# main.net
KiCad netlist of a schematic drawn in Altium Designer
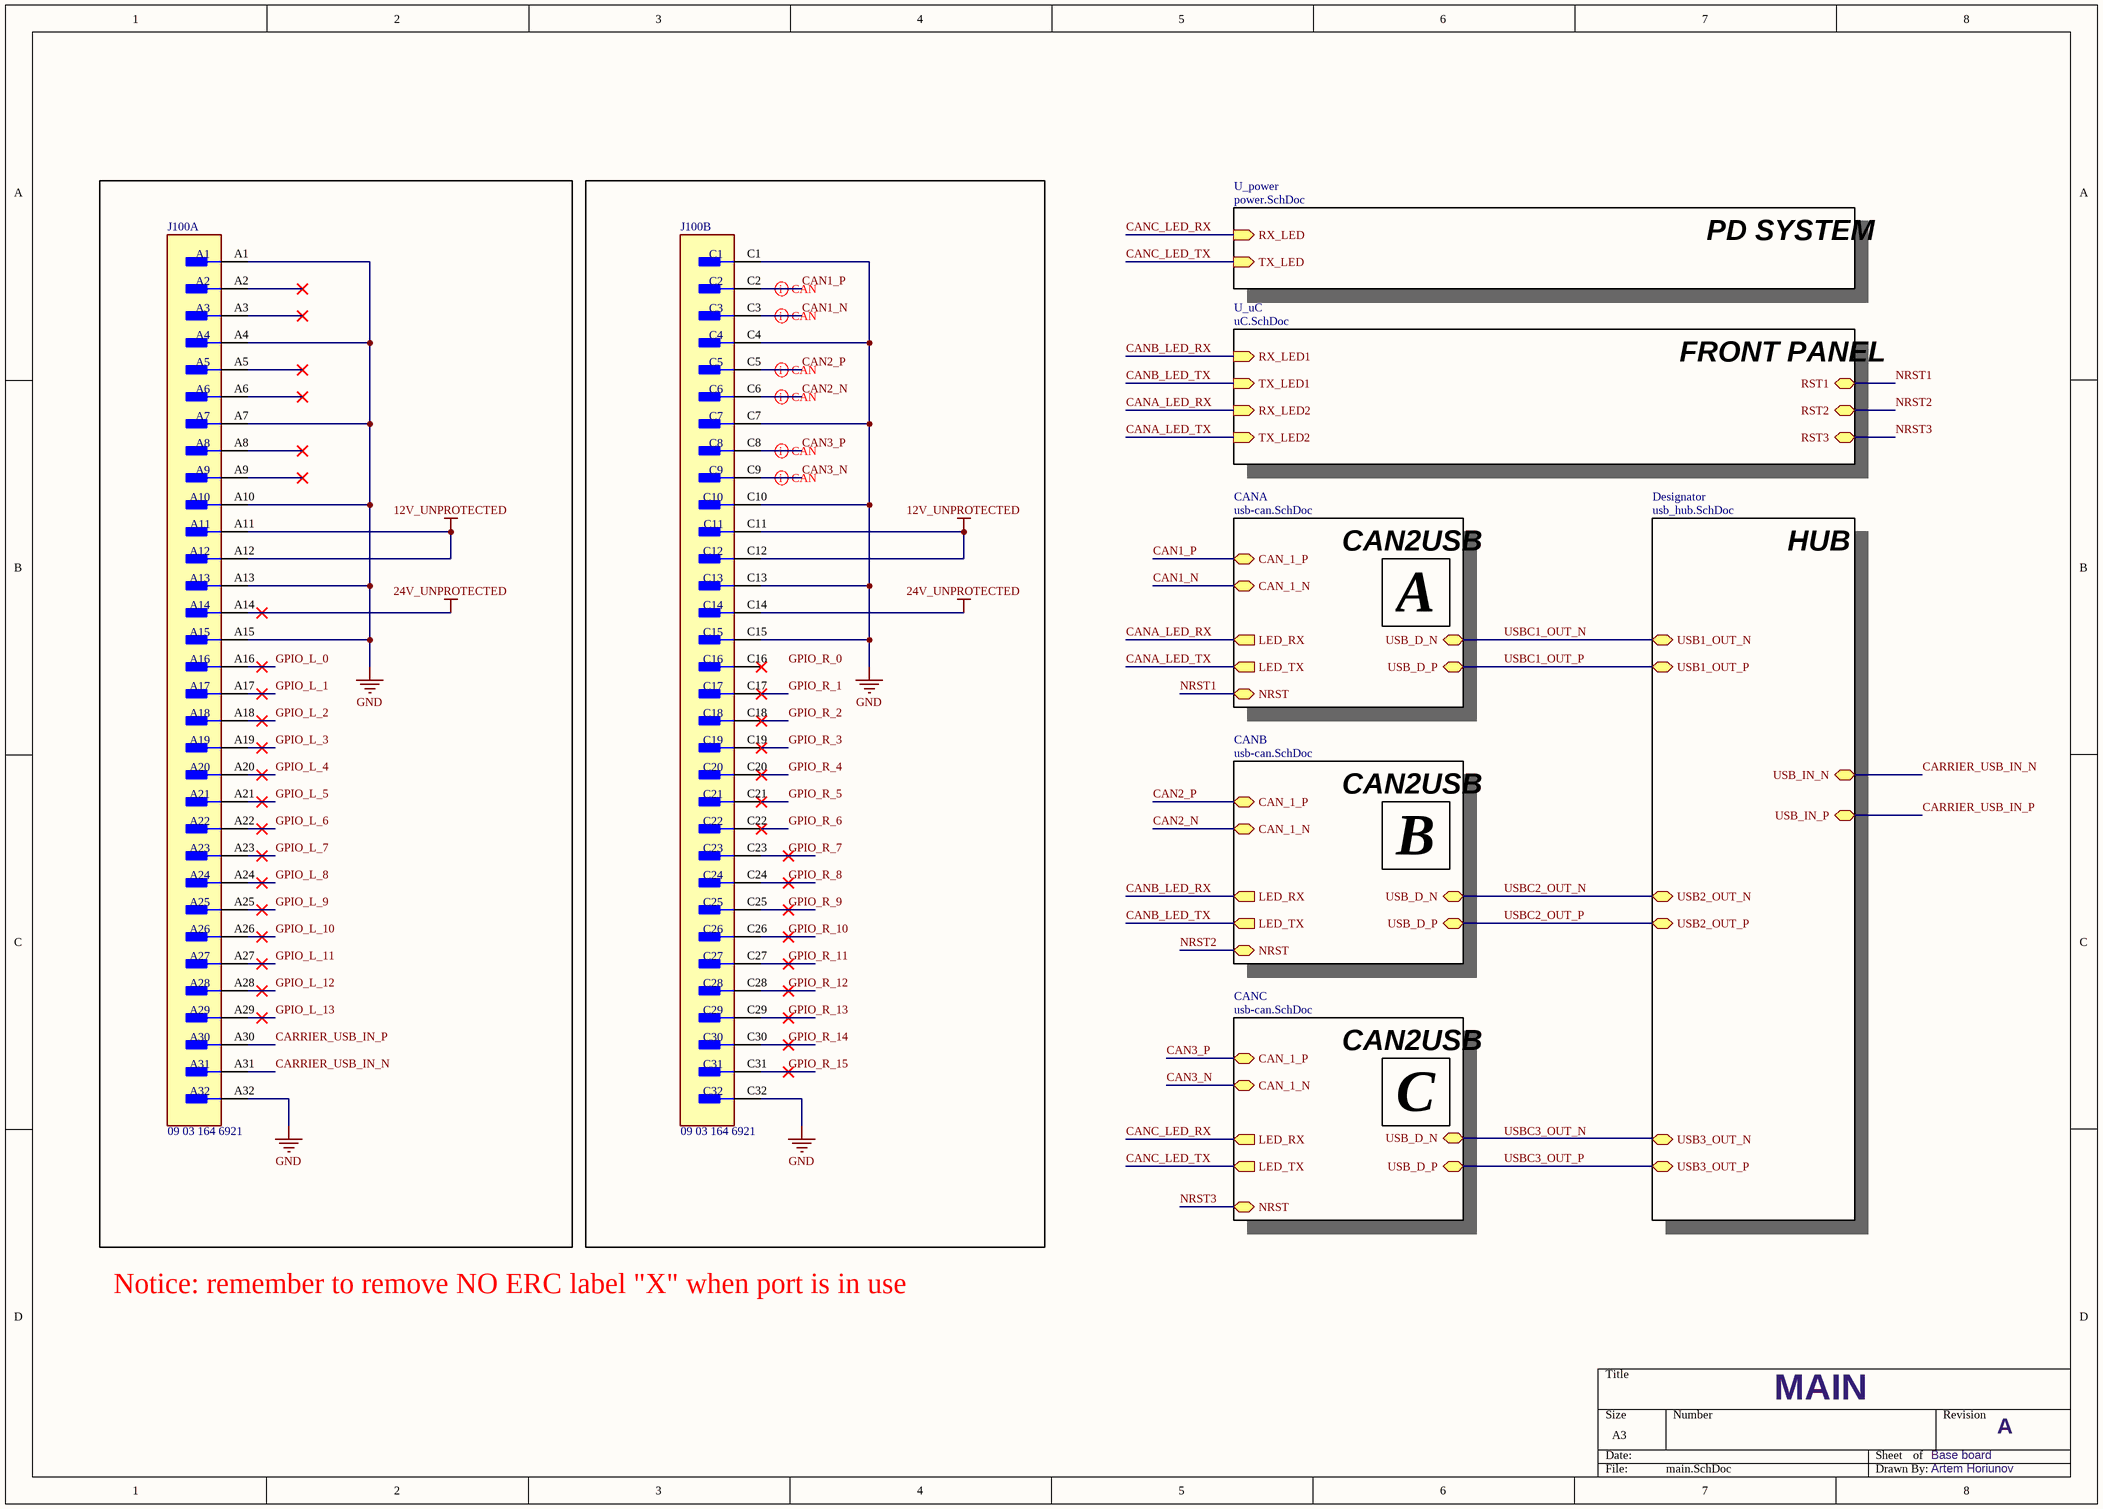
[diagram p0: main.SchDoc]

(export (version "E")
  (design (tool "Eeschema 10.0.6"))
  (components
    (comp (ref "J100")
      (value "09 03 164 6921")
      (footprint "FP-09_03_164_6921-MFG")
      (description "CONN DIN HDR 96POS PCB RA")
      (fields
        (field (name "MANUFACTURER") "Harting")
        (field (name "OCTOPART") "https://octopart.com/09031646921-harting+elektronik-42933")
      )
      (libsource (lib "Altium Content Vault") (part "242112e785ae82ea23b0e3c1eadb5b2"))
    )
  )
  (nets
    (net (code "2") (name "/CAN1_N") (class "Default")
      (node (ref "J100") (pin "C3") (pinfunction "C3_C3") (pintype "passive"))
    )
    (net (code "3") (name "/CAN1_P") (class "Default")
      (node (ref "J100") (pin "C2") (pinfunction "C2_C2") (pintype "passive"))
    )
    (net (code "4") (name "/CAN2_N") (class "Default")
      (node (ref "J100") (pin "C6") (pinfunction "C6_C6") (pintype "passive"))
    )
    (net (code "5") (name "/CAN2_P") (class "Default")
      (node (ref "J100") (pin "C5") (pinfunction "C5_C5") (pintype "passive"))
    )
    (net (code "6") (name "/CAN3_N") (class "Default")
      (node (ref "J100") (pin "C9") (pinfunction "C9_C9") (pintype "passive"))
    )
    (net (code "7") (name "/CAN3_P") (class "Default")
      (node (ref "J100") (pin "C8") (pinfunction "C8_C8") (pintype "passive"))
    )
    (net (code "14") (name "/CARRIER_USB_IN_N") (class "Default")
      (node (ref "J100") (pin "A31") (pinfunction "A31_A31") (pintype "passive"))
    )
    (net (code "15") (name "/CARRIER_USB_IN_P") (class "Default")
      (node (ref "J100") (pin "A30") (pinfunction "A30_A30") (pintype "passive"))
    )
    (net (code "16") (name "/GPIO_L_0") (class "Default")
      (node (ref "J100") (pin "A16") (pinfunction "A16_A16") (pintype "passive"))
    )
    (net (code "17") (name "/GPIO_L_1") (class "Default")
      (node (ref "J100") (pin "A17") (pinfunction "A17_A17") (pintype "passive"))
    )
    (net (code "18") (name "/GPIO_L_2") (class "Default")
      (node (ref "J100") (pin "A18") (pinfunction "A18_A18") (pintype "passive"))
    )
    (net (code "19") (name "/GPIO_L_3") (class "Default")
      (node (ref "J100") (pin "A19") (pinfunction "A19_A19") (pintype "passive"))
    )
    (net (code "20") (name "/GPIO_L_4") (class "Default")
      (node (ref "J100") (pin "A20") (pinfunction "A20_A20") (pintype "passive"))
    )
    (net (code "21") (name "/GPIO_L_5") (class "Default")
      (node (ref "J100") (pin "A21") (pinfunction "A21_A21") (pintype "passive"))
    )
    (net (code "22") (name "/GPIO_L_6") (class "Default")
      (node (ref "J100") (pin "A22") (pinfunction "A22_A22") (pintype "passive"))
    )
    (net (code "23") (name "/GPIO_L_7") (class "Default")
      (node (ref "J100") (pin "A23") (pinfunction "A23_A23") (pintype "passive"))
    )
    (net (code "24") (name "/GPIO_L_8") (class "Default")
      (node (ref "J100") (pin "A24") (pinfunction "A24_A24") (pintype "passive"))
    )
    (net (code "25") (name "/GPIO_L_9") (class "Default")
      (node (ref "J100") (pin "A25") (pinfunction "A25_A25") (pintype "passive"))
    )
    (net (code "26") (name "/GPIO_L_10") (class "Default")
      (node (ref "J100") (pin "A26") (pinfunction "A26_A26") (pintype "passive"))
    )
    (net (code "27") (name "/GPIO_L_11") (class "Default")
      (node (ref "J100") (pin "A27") (pinfunction "A27_A27") (pintype "passive"))
    )
    (net (code "28") (name "/GPIO_L_12") (class "Default")
      (node (ref "J100") (pin "A28") (pinfunction "A28_A28") (pintype "passive"))
    )
    (net (code "29") (name "/GPIO_L_13") (class "Default")
      (node (ref "J100") (pin "A29") (pinfunction "A29_A29") (pintype "passive"))
    )
    (net (code "31") (name "/GPIO_R_1") (class "Default")
      (node (ref "J100") (pin "C17") (pinfunction "C17_C17") (pintype "passive+no_connect"))
    )
    (net (code "32") (name "/GPIO_R_2") (class "Default")
      (node (ref "J100") (pin "C18") (pinfunction "C18_C18") (pintype "passive+no_connect"))
    )
    (net (code "33") (name "/GPIO_R_3") (class "Default")
      (node (ref "J100") (pin "C19") (pinfunction "C19_C19") (pintype "passive+no_connect"))
    )
    (net (code "34") (name "/GPIO_R_4") (class "Default")
      (node (ref "J100") (pin "C20") (pinfunction "C20_C20") (pintype "passive+no_connect"))
    )
    (net (code "35") (name "/GPIO_R_5") (class "Default")
      (node (ref "J100") (pin "C21") (pinfunction "C21_C21") (pintype "passive+no_connect"))
    )
    (net (code "36") (name "/GPIO_R_6") (class "Default")
      (node (ref "J100") (pin "C22") (pinfunction "C22_C22") (pintype "passive+no_connect"))
    )
    (net (code "55") (name "/GPIO_R_7") (class "Default")
      (node (ref "J100") (pin "C23") (pinfunction "C23_C23") (pintype "passive"))
    )
    (net (code "56") (name "/GPIO_R_8") (class "Default")
      (node (ref "J100") (pin "C24") (pinfunction "C24_C24") (pintype "passive"))
    )
    (net (code "57") (name "/GPIO_R_9") (class "Default")
      (node (ref "J100") (pin "C25") (pinfunction "C25_C25") (pintype "passive"))
    )
    (net (code "58") (name "/GPIO_R_10") (class "Default")
      (node (ref "J100") (pin "C26") (pinfunction "C26_C26") (pintype "passive"))
    )
    (net (code "59") (name "/GPIO_R_11") (class "Default")
      (node (ref "J100") (pin "C27") (pinfunction "C27_C27") (pintype "passive"))
    )
    (net (code "60") (name "/GPIO_R_12") (class "Default")
      (node (ref "J100") (pin "C28") (pinfunction "C28_C28") (pintype "passive"))
    )
    (net (code "61") (name "/GPIO_R_13") (class "Default")
      (node (ref "J100") (pin "C29") (pinfunction "C29_C29") (pintype "passive"))
    )
    (net (code "62") (name "/GPIO_R_14") (class "Default")
      (node (ref "J100") (pin "C30") (pinfunction "C30_C30") (pintype "passive"))
    )
    (net (code "63") (name "/GPIO_R_15") (class "Default")
      (node (ref "J100") (pin "C31") (pinfunction "C31_C31") (pintype "passive"))
    )
    (net (code "64") (name "12V_UNPROTECTED") (class "Default")
      (node (ref "J100") (pin "A11") (pinfunction "A11_A11") (pintype "passive"))
      (node (ref "J100") (pin "A12") (pinfunction "A12_A12") (pintype "passive"))
      (node (ref "J100") (pin "C11") (pinfunction "C11_C11") (pintype "passive"))
      (node (ref "J100") (pin "C12") (pinfunction "C12_C12") (pintype "passive"))
    )
    (net (code "65") (name "24V_UNPROTECTED") (class "Default")
      (node (ref "J100") (pin "A14") (pinfunction "A14_A14") (pintype "passive"))
      (node (ref "J100") (pin "C14") (pinfunction "C14_C14") (pintype "passive"))
    )
    (net (code "66") (name "GND") (class "Default")
      (node (ref "J100") (pin "A1") (pinfunction "A1_A1") (pintype "passive"))
      (node (ref "J100") (pin "A10") (pinfunction "A10_A10") (pintype "passive"))
      (node (ref "J100") (pin "A13") (pinfunction "A13_A13") (pintype "passive"))
      (node (ref "J100") (pin "A15") (pinfunction "A15_A15") (pintype "passive"))
      (node (ref "J100") (pin "A32") (pinfunction "A32_A32") (pintype "passive"))
      (node (ref "J100") (pin "A4") (pinfunction "A4_A4") (pintype "passive"))
      (node (ref "J100") (pin "A7") (pinfunction "A7_A7") (pintype "passive"))
      (node (ref "J100") (pin "C1") (pinfunction "C1_C1") (pintype "passive"))
      (node (ref "J100") (pin "C10") (pinfunction "C10_C10") (pintype "passive"))
      (node (ref "J100") (pin "C13") (pinfunction "C13_C13") (pintype "passive"))
      (node (ref "J100") (pin "C15") (pinfunction "C15_C15") (pintype "passive"))
      (node (ref "J100") (pin "C32") (pinfunction "C32_C32") (pintype "passive"))
      (node (ref "J100") (pin "C4") (pinfunction "C4_C4") (pintype "passive"))
      (node (ref "J100") (pin "C7") (pinfunction "C7_C7") (pintype "passive"))
    )
    (net (code "67") (name "unconnected-(J100-PadA2)") (class "Default")
      (node (ref "J100") (pin "A2") (pinfunction "A2_A2") (pintype "passive+no_connect"))
    )
    (net (code "68") (name "unconnected-(J100-PadA3)") (class "Default")
      (node (ref "J100") (pin "A3") (pinfunction "A3_A3") (pintype "passive+no_connect"))
    )
    (net (code "69") (name "unconnected-(J100-PadA5)") (class "Default")
      (node (ref "J100") (pin "A5") (pinfunction "A5_A5") (pintype "passive+no_connect"))
    )
    (net (code "70") (name "unconnected-(J100-PadA6)") (class "Default")
      (node (ref "J100") (pin "A6") (pinfunction "A6_A6") (pintype "passive+no_connect"))
    )
    (net (code "71") (name "unconnected-(J100-PadA8)") (class "Default")
      (node (ref "J100") (pin "A8") (pinfunction "A8_A8") (pintype "passive+no_connect"))
    )
    (net (code "72") (name "unconnected-(J100-PadA9)") (class "Default")
      (node (ref "J100") (pin "A9") (pinfunction "A9_A9") (pintype "passive+no_connect"))
    )
    (net (code "73") (name "unconnected-(J100-PadC16)") (class "Default")
      (node (ref "J100") (pin "C16") (pinfunction "C16_C16") (pintype "passive+no_connect"))
    )
  )
)
